# ADF_1st_mixer_TX.net
KiCad netlist of a schematic drawn in Altium Designer
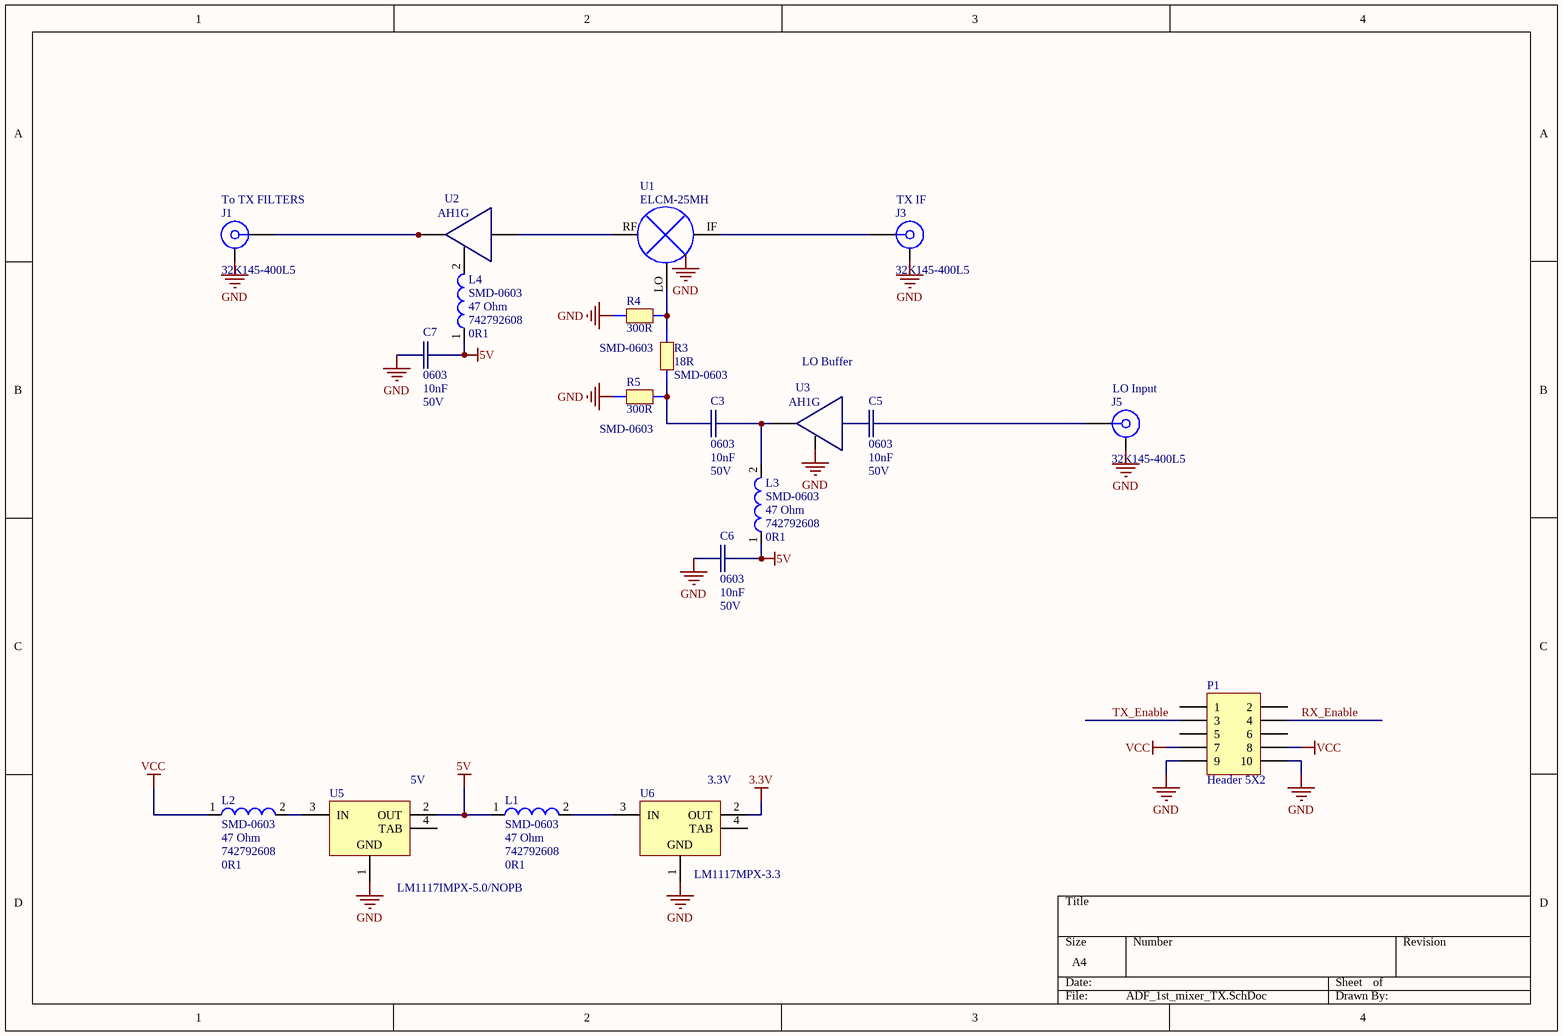
[diagram p0: ADF_1st_mixer_TX.SchDoc]

(export (version "E")
  (design (tool "Eeschema 10.0.6"))
  (components
    (comp (ref "C3")
      (value "10nF 0603 NP0")
      (footprint "C0603_murata")
      (description "10nF 0603 NP0 muRata")
      (fields
        (field (name "TOLERANCE") "5%")
        (field (name "CASE CODE (IMPERIAL)") "0603")
        (field (name "CAPACITANCE") "10nF")
        (field (name "VOLTAGE") "50V")
      )
      (libsource (lib "ftg_lib") (part "10nF 0603 NP0"))
    )
    (comp (ref "C5")
      (value "10nF 0603 NP0")
      (footprint "C0603_murata")
      (description "10nF 0603 NP0 muRata")
      (fields
        (field (name "TOLERANCE") "5%")
        (field (name "CASE CODE (IMPERIAL)") "0603")
        (field (name "CAPACITANCE") "10nF")
        (field (name "VOLTAGE") "50V")
      )
      (libsource (lib "ftg_lib") (part "10nF 0603 NP0"))
    )
    (comp (ref "C6")
      (value "10nF 0603 NP0")
      (footprint "C0603_murata")
      (description "10nF 0603 NP0 muRata")
      (fields
        (field (name "TOLERANCE") "5%")
        (field (name "CASE CODE (IMPERIAL)") "0603")
        (field (name "CAPACITANCE") "10nF")
        (field (name "VOLTAGE") "50V")
      )
      (libsource (lib "ftg_lib") (part "10nF 0603 NP0"))
    )
    (comp (ref "C7")
      (value "10nF 0603 NP0")
      (footprint "C0603_murata")
      (description "10nF 0603 NP0 muRata")
      (fields
        (field (name "TOLERANCE") "5%")
        (field (name "CASE CODE (IMPERIAL)") "0603")
        (field (name "CAPACITANCE") "10nF")
        (field (name "VOLTAGE") "50V")
      )
      (libsource (lib "ftg_lib") (part "10nF 0603 NP0"))
    )
    (comp (ref "J1")
      (value "32K145-400L5")
      (footprint "ROS-32K145-400L5_V")
      (description "SMA Right Angle Jack, Edge Mount, Up to 18 GHz, -55 to 155 degC")
      (libsource (lib "Rosenberger SMA") (part "32K145-400L5"))
    )
    (comp (ref "J3")
      (value "32K145-400L5")
      (footprint "ROS-32K145-400L5_V")
      (description "SMA Right Angle Jack, Edge Mount, Up to 18 GHz, -55 to 155 degC")
      (libsource (lib "Rosenberger SMA") (part "32K145-400L5"))
    )
    (comp (ref "J5")
      (value "32K145-400L5")
      (footprint "ROS-32K145-400L5_V")
      (description "SMA Right Angle Jack, Edge Mount, Up to 18 GHz, -55 to 155 degC")
      (libsource (lib "Rosenberger SMA") (part "32K145-400L5"))
    )
    (comp (ref "L1")
      (value "742792608")
      (footprint "SMD-0603")
      (description "SMD EMI Suppression Ferrite Bead WE-CBF, Z = 47 Ohm")
      (fields
        (field (name "PACKAGEREFERENCE") "SMD-0603")
        (field (name "IMPEDANCE") "47 Ohm")
        (field (name "DC_RESISTANCE") "0R1")
      )
      (libsource (lib "AQA_20007_4_Flange") (part "742792608"))
    )
    (comp (ref "L2")
      (value "742792608")
      (footprint "SMD-0603")
      (description "SMD EMI Suppression Ferrite Bead WE-CBF, Z = 47 Ohm")
      (fields
        (field (name "PACKAGEREFERENCE") "SMD-0603")
        (field (name "IMPEDANCE") "47 Ohm")
        (field (name "DC_RESISTANCE") "0R1")
      )
      (libsource (lib "AQA_20007_4_Flange") (part "742792608"))
    )
    (comp (ref "L3")
      (value "742792608")
      (footprint "SMD-0603")
      (description "SMD EMI Suppression Ferrite Bead WE-CBF, Z = 47 Ohm")
      (fields
        (field (name "PACKAGEREFERENCE") "SMD-0603")
        (field (name "IMPEDANCE") "47 Ohm")
        (field (name "DC_RESISTANCE") "0R1")
      )
      (libsource (lib "AQA_20007_4_Flange") (part "742792608"))
    )
    (comp (ref "L4")
      (value "742792608")
      (footprint "SMD-0603")
      (description "SMD EMI Suppression Ferrite Bead WE-CBF, Z = 47 Ohm")
      (fields
        (field (name "PACKAGEREFERENCE") "SMD-0603")
        (field (name "IMPEDANCE") "47 Ohm")
        (field (name "DC_RESISTANCE") "0R1")
      )
      (libsource (lib "AQA_20007_4_Flange") (part "742792608"))
    )
    (comp (ref "P1")
      (value "Header 5X2")
      (footprint "HDR2X5")
      (description "Header, 5-Pin, Dual row")
      (fields (field (name "PUBLISHER") "Altium Limited"))
      (libsource (lib "Miscellaneous Connectors") (part "Header 5X2"))
    )
    (comp (ref "R3")
      (value "18R")
      (footprint "RESC1608X06N_0603")
      (description "Bulk SMD Resistor")
      (fields
        (field (name "MANUFACTURER") "PANASONIC")
        (field (name "VOLTAGE") "75V")
        (field (name "PACKAGEREFERENCE") "SMD-0603")
        (field (name "PUBLISHER") "atr")
      )
      (libsource (lib "") (part "Resistor_0R_0603_Bulk_1"))
    )
    (comp (ref "R4")
      (value "300R")
      (footprint "RESC1608X06N_0603")
      (description "Bulk SMD Resistor")
      (fields
        (field (name "MANUFACTURER") "PANASONIC")
        (field (name "VOLTAGE") "75V")
        (field (name "PACKAGEREFERENCE") "SMD-0603")
        (field (name "PUBLISHER") "atr")
      )
      (libsource (lib "AQA_atr_2013") (part "Resistor_0R_0603_Bulk"))
    )
    (comp (ref "R5")
      (value "300R")
      (footprint "RESC1608X06N_0603")
      (description "Bulk SMD Resistor")
      (fields
        (field (name "MANUFACTURER") "PANASONIC")
        (field (name "VOLTAGE") "75V")
        (field (name "PACKAGEREFERENCE") "SMD-0603")
        (field (name "PUBLISHER") "atr")
      )
      (libsource (lib "AQA_atr_2013") (part "Resistor_0R_0603_Bulk"))
    )
    (comp (ref "U1") (value "ELCM-25MH") (footprint "SM-87") (libsource (lib "ftg_lib") (part "ELCM-25MH")))
    (comp (ref "U2")
      (value "AH1G")
      (footprint "SOT-89")
      (description "250-4000MHz MMIC")
      (libsource (lib "ftg_lib") (part "AH1G"))
    )
    (comp (ref "U3")
      (value "AH1G")
      (footprint "SOT-89")
      (description "250-4000MHz MMIC")
      (libsource (lib "ftg_lib") (part "AH1G"))
    )
    (comp (ref "U5")
      (value "LM1117IMPX-5.0/NOPB")
      (footprint "MP04A_M")
      (description "800mA Low-Dropout Linear Regulator, 4-pin SOT-223, Pb-Free")
      (fields (field (name "MANUFACTURER") "National Semiconductor"))
      (libsource (lib "Altium Content Vault") (part "PM-REG-LM1086-SOT4"))
    )
    (comp (ref "U6")
      (value "LM1117MPX-3.3")
      (footprint "DCY0004A_N")
      (description "800mA Low-Dropout Linear Regulator, 4-pin SOT-223")
      (fields (field (name "MANUFACTURER") "Texas Instruments"))
      (libsource (lib "Altium Content Vault") (part "PM-REG-LM1086-SOT4"))
    )
  )
  (nets
    (net (code "1") (name "/RX_Enable") (class "Default")
      (node (ref "P1") (pin "4") (pinfunction "4_4") (pintype "passive"))
    )
    (net (code "2") (name "/TX_Enable") (class "Default")
      (node (ref "P1") (pin "3") (pinfunction "3_3") (pintype "passive"))
    )
    (net (code "3") (name "3.3V") (class "Default")
      (node (ref "U6") (pin "2") (pinfunction "OUT_2") (pintype "power_in"))
    )
    (net (code "4") (name "5V") (class "Default")
      (node (ref "C6") (pin "2") (pinfunction "2_2") (pintype "passive"))
      (node (ref "C7") (pin "2") (pinfunction "2_2") (pintype "passive"))
      (node (ref "L1") (pin "1") (pinfunction "1_1") (pintype "passive"))
      (node (ref "L3") (pin "1") (pinfunction "1_1") (pintype "passive"))
      (node (ref "L4") (pin "1") (pinfunction "1_1") (pintype "passive"))
      (node (ref "U5") (pin "2") (pinfunction "OUT_2") (pintype "power_in"))
    )
    (net (code "5") (name "GND") (class "Default")
      (node (ref "C6") (pin "1") (pinfunction "1_1") (pintype "passive"))
      (node (ref "C7") (pin "1") (pinfunction "1_1") (pintype "passive"))
      (node (ref "J1") (pin "MP") (pinfunction "MP_MP") (pintype "passive"))
      (node (ref "J3") (pin "MP") (pinfunction "MP_MP") (pintype "passive"))
      (node (ref "J5") (pin "MP") (pinfunction "MP_MP") (pintype "passive"))
      (node (ref "P1") (pin "10") (pinfunction "10_10") (pintype "passive"))
      (node (ref "P1") (pin "9") (pinfunction "9_9") (pintype "passive"))
      (node (ref "R4") (pin "2") (pinfunction "2_2") (pintype "passive"))
      (node (ref "R5") (pin "2") (pinfunction "2_2") (pintype "passive"))
      (node (ref "U1") (pin "GND") (pinfunction "GND_GND") (pintype "passive"))
      (node (ref "U3") (pin "2") (pinfunction "2_2") (pintype "passive"))
      (node (ref "U5") (pin "1") (pinfunction "GND_1") (pintype "power_in"))
      (node (ref "U6") (pin "1") (pinfunction "GND_1") (pintype "power_in"))
    )
    (net (code "6") (name "Net-(C3-Pad1)") (class "Default")
      (node (ref "C3") (pin "1") (pinfunction "1_1") (pintype "passive"))
      (node (ref "R3") (pin "1") (pinfunction "1_1") (pintype "passive"))
      (node (ref "R5") (pin "1") (pinfunction "1_1") (pintype "passive"))
    )
    (net (code "7") (name "Net-(C3-Pad2)") (class "Default")
      (node (ref "C3") (pin "2") (pinfunction "2_2") (pintype "passive"))
      (node (ref "L3") (pin "2") (pinfunction "2_2") (pintype "passive"))
      (node (ref "U3") (pin "3") (pinfunction "3_3") (pintype "passive"))
    )
    (net (code "8") (name "Net-(C5-Pad1)") (class "Default")
      (node (ref "C5") (pin "1") (pinfunction "1_1") (pintype "passive"))
      (node (ref "U3") (pin "1") (pinfunction "1_1") (pintype "passive"))
    )
    (net (code "9") (name "Net-(C5-Pad2)") (class "Default")
      (node (ref "C5") (pin "2") (pinfunction "2_2") (pintype "passive"))
      (node (ref "J5") (pin "1") (pinfunction "1_1") (pintype "passive"))
    )
    (net (code "10") (name "Net-(J1-Pad1)") (class "Default")
      (node (ref "J1") (pin "1") (pinfunction "1_1") (pintype "passive"))
      (node (ref "U2") (pin "3") (pinfunction "3_3") (pintype "passive"))
    )
    (net (code "11") (name "Net-(J3-Pad1)") (class "Default")
      (node (ref "J3") (pin "1") (pinfunction "1_1") (pintype "passive"))
      (node (ref "U1") (pin "IF") (pinfunction "IF_IF") (pintype "passive"))
    )
    (net (code "12") (name "Net-(L4-Pad2)") (class "Default")
      (node (ref "L4") (pin "2") (pinfunction "2_2") (pintype "passive"))
      (node (ref "U2") (pin "2") (pinfunction "2_2") (pintype "passive"))
    )
    (net (code "13") (name "Net-(R3-Pad2)") (class "Default")
      (node (ref "R3") (pin "2") (pinfunction "2_2") (pintype "passive"))
      (node (ref "R4") (pin "1") (pinfunction "1_1") (pintype "passive"))
      (node (ref "U1") (pin "LO") (pinfunction "LO_LO") (pintype "passive"))
    )
    (net (code "14") (name "Net-(U5-IN)") (class "Default")
      (node (ref "L2") (pin "2") (pinfunction "2_2") (pintype "passive"))
      (node (ref "U5") (pin "3") (pinfunction "IN_3") (pintype "power_in"))
    )
    (net (code "15") (name "Net-(U6-IN)") (class "Default")
      (node (ref "L1") (pin "2") (pinfunction "2_2") (pintype "passive"))
      (node (ref "U6") (pin "3") (pinfunction "IN_3") (pintype "power_in"))
    )
    (net (code "16") (name "VCC") (class "Default")
      (node (ref "L2") (pin "1") (pinfunction "1_1") (pintype "passive"))
      (node (ref "P1") (pin "7") (pinfunction "7_7") (pintype "passive"))
      (node (ref "P1") (pin "8") (pinfunction "8_8") (pintype "passive"))
    )
    (net (code "17") (name "unconnected-(P1-Pad1)") (class "Default")
      (node (ref "P1") (pin "1") (pinfunction "1_1") (pintype "passive"))
    )
    (net (code "18") (name "unconnected-(P1-Pad2)") (class "Default")
      (node (ref "P1") (pin "2") (pinfunction "2_2") (pintype "passive"))
    )
    (net (code "19") (name "unconnected-(P1-Pad5)") (class "Default")
      (node (ref "P1") (pin "5") (pinfunction "5_5") (pintype "passive"))
    )
    (net (code "20") (name "unconnected-(P1-Pad6)") (class "Default")
      (node (ref "P1") (pin "6") (pinfunction "6_6") (pintype "passive"))
    )
    (net (code "21") (name "unconnected-(U1-PadRF)") (class "Default")
      (node (ref "U1") (pin "RF") (pinfunction "RF_RF") (pintype "passive"))
    )
    (net (code "22") (name "unconnected-(U2-Pad1)") (class "Default")
      (node (ref "U2") (pin "1") (pinfunction "1_1") (pintype "passive"))
    )
    (net (code "23") (name "unconnected-(U5-TAB-Pad4)") (class "Default")
      (node (ref "U5") (pin "4") (pinfunction "TAB_4") (pintype "power_in"))
    )
    (net (code "24") (name "unconnected-(U6-TAB-Pad4)") (class "Default")
      (node (ref "U6") (pin "4") (pinfunction "TAB_4") (pintype "power_in"))
    )
  )
)
